# plugV8-Relay-NO-Dummy_Board.net
KiCad netlist of a schematic drawn in EAGLE
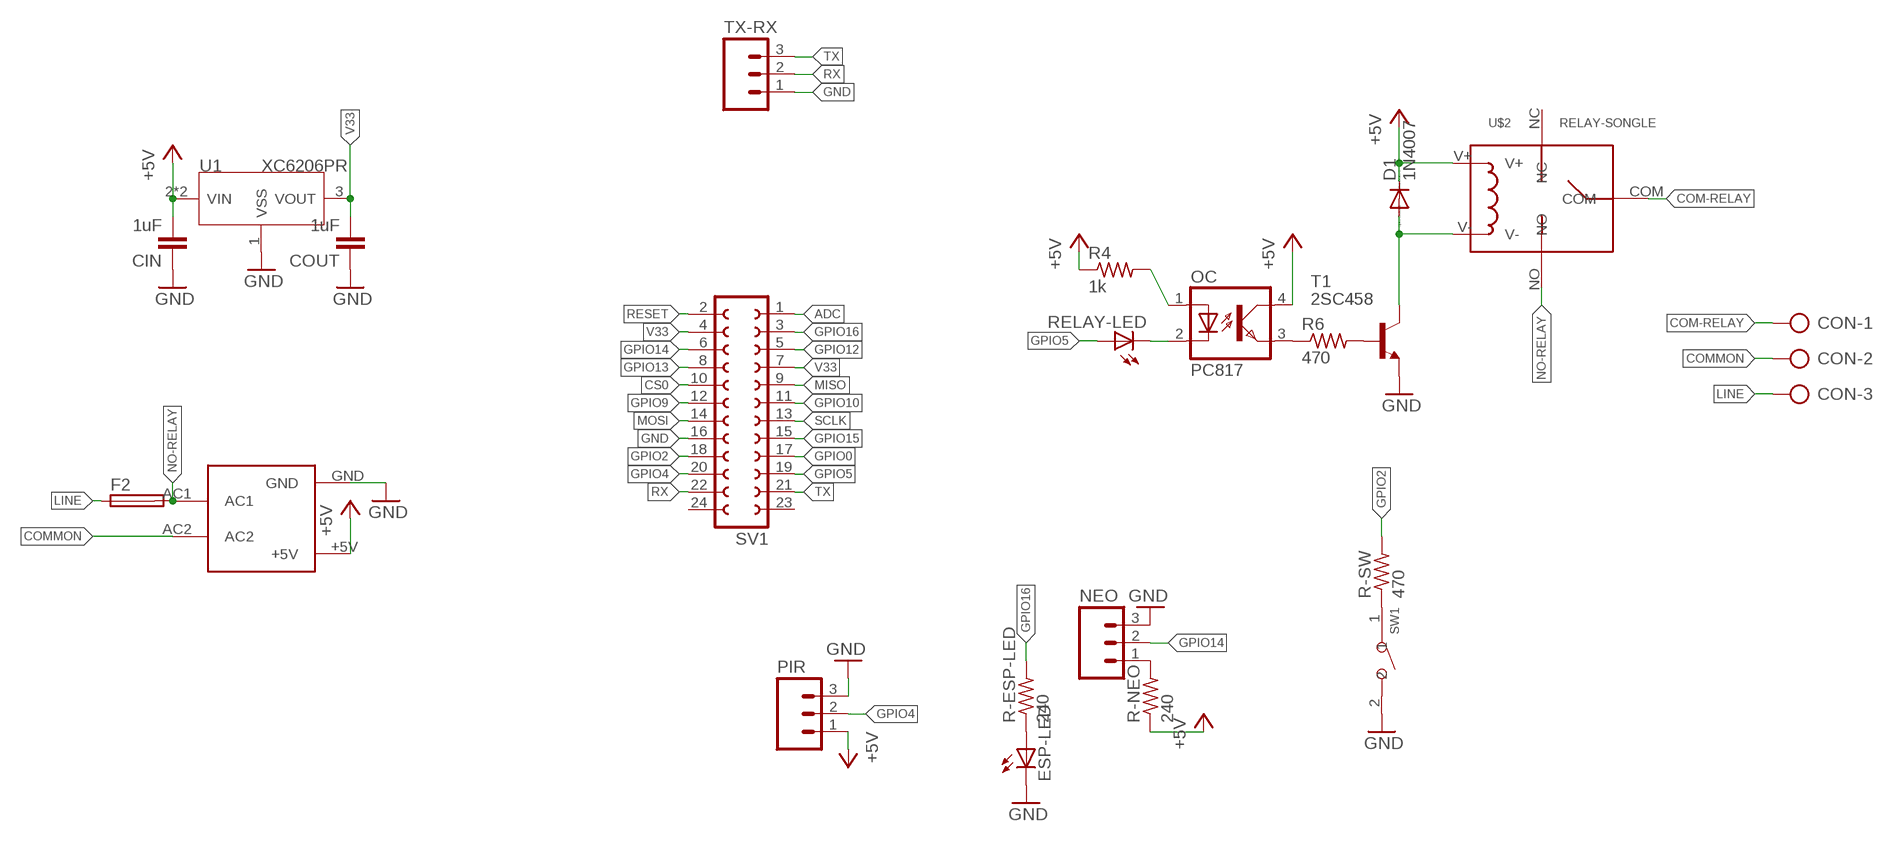
[diagram p0: schematic, sheet 1]

(export (version "E")
  (design (tool "Eeschema 10.0.6"))
  (components
    (comp (ref "CIN")
      (value "1uF")
      (footprint "eagle-import:C0805")
      (libsource (lib "eagle-import") (part "C-EUC0805"))
    )
    (comp (ref "CON")
      (value "AK300/3")
      (footprint "eagle-import:AK300_3")
      (libsource (lib "eagle-import") (part "AK300/3"))
    )
    (comp (ref "COUT")
      (value "1uF")
      (footprint "eagle-import:C0805")
      (libsource (lib "eagle-import") (part "C-EUC0805"))
    )
    (comp (ref "D1")
      (value "1N4007")
      (footprint "eagle-import:DO41-10")
      (libsource (lib "eagle-import") (part "1N4004"))
    )
    (comp (ref "ESP-LED")
      (value "LED3MM")
      (footprint "eagle-import:LED3MM")
      (libsource (lib "eagle-import") (part "LED3MM"))
    )
    (comp (ref "F2")
      (value "TR5")
      (footprint "eagle-import:TR5")
      (libsource (lib "eagle-import") (part "TR5"))
    )
    (comp (ref "NEO")
      (value "M03PTH")
      (footprint "eagle-import:1X03")
      (libsource (lib "eagle-import") (part "M03PTH"))
    )
    (comp (ref "OC")
      (value "PC817")
      (footprint "eagle-import:DIL04")
      (fields (field (name "MPN") "PC817X4J000F"))
      (libsource (lib "eagle-import") (part "PC817"))
    )
    (comp (ref "PIR")
      (value "M03PTH")
      (footprint "eagle-import:1X03")
      (libsource (lib "eagle-import") (part "M03PTH"))
    )
    (comp (ref "R-ESP-LED")
      (value "240")
      (footprint "eagle-import:0204_7")
      (libsource (lib "eagle-import") (part "R-US_0204/7"))
    )
    (comp (ref "R-NEO")
      (value "240")
      (footprint "eagle-import:0204_7")
      (libsource (lib "eagle-import") (part "R-US_0204/7"))
    )
    (comp (ref "R-SW")
      (value "470")
      (footprint "eagle-import:0204_7")
      (libsource (lib "eagle-import") (part "R-US_0204/7"))
    )
    (comp (ref "R4")
      (value "1k")
      (footprint "eagle-import:0204_7")
      (libsource (lib "eagle-import") (part "R-US_0204/7"))
    )
    (comp (ref "R6")
      (value "470")
      (footprint "eagle-import:0204_7")
      (libsource (lib "eagle-import") (part "R-US_0204/7"))
    )
    (comp (ref "RELAY-LED")
      (value "LED3MM")
      (footprint "eagle-import:LED3MM")
      (libsource (lib "eagle-import") (part "LED3MM"))
    )
    (comp (ref "SV1")
      (value "FE12-2")
      (footprint "eagle-import:FE12-2")
      (libsource (lib "eagle-import") (part "FE12-2"))
    )
    (comp (ref "SW1")
      (value "DIP-BUTTON(2P-6.0X3.0X4.3MM)-TS-1101F")
      (footprint "eagle-import:SW2-5.0-6.0X3.0X4.3MM")
      (libsource (lib "eagle-import") (part "DIP-BUTTON(2P-6.0X3.0X4.3MM)-TS-1101F"))
    )
    (comp (ref "T1")
      (value "2SC458")
      (footprint "eagle-import:TO92-ECB")
      (libsource (lib "eagle-import") (part "2SC458"))
    )
    (comp (ref "TX-RX")
      (value "M03PTH")
      (footprint "eagle-import:1X03")
      (libsource (lib "eagle-import") (part "M03PTH"))
    )
    (comp (ref "U$1")
      (value "HLK-PM01")
      (footprint "eagle-import:HLK-PM01")
      (libsource (lib "eagle-import") (part "HLK-PM01"))
    )
    (comp (ref "U$2")
      (value "RELAY-SONGLE")
      (footprint "eagle-import:RELAY-SONGLE")
      (libsource (lib "eagle-import") (part "RELAY-SONGLE"))
    )
    (comp (ref "U1")
      (value "XC6206PR")
      (footprint "eagle-import:SOT89")
      (libsource (lib "eagle-import") (part "XC6206PR"))
    )
  )
  (nets
    (net (code "1") (name "+5V") (class "Default")
      (node (ref "CIN") (pin "2") (pinfunction "2_2") (pintype "passive"))
      (node (ref "D1") (pin "C") (pinfunction "C_C") (pintype "passive"))
      (node (ref "OC") (pin "4") (pinfunction "COL_4") (pintype "passive"))
      (node (ref "PIR") (pin "1") (pinfunction "1_1") (pintype "passive"))
      (node (ref "R-NEO") (pin "1") (pinfunction "1_1") (pintype "passive"))
      (node (ref "R4") (pin "1") (pinfunction "1_1") (pintype "passive"))
      (node (ref "U$1") (pin "+5V") (pinfunction "+5V_+5V") (pintype "bidirectional"))
      (node (ref "U$2") (pin "V+") (pinfunction "V+_V+") (pintype "bidirectional"))
      (node (ref "U1") (pin "2") (pinfunction "VIN_2") (pintype "input"))
      (node (ref "U1") (pin "4") (pinfunction "VIN_4") (pintype "input"))
    )
    (net (code "2") (name "ADC") (class "Default")
      (node (ref "SV1") (pin "1") (pinfunction "1_1") (pintype "passive"))
    )
    (net (code "3") (name "COM-RELAY") (class "Default")
      (node (ref "CON") (pin "1") (pinfunction "KL_1") (pintype "passive"))
      (node (ref "U$2") (pin "COM") (pinfunction "COM_COM") (pintype "bidirectional"))
    )
    (net (code "4") (name "COMMON") (class "Default")
      (node (ref "CON") (pin "2") (pinfunction "KL_2") (pintype "passive"))
      (node (ref "U$1") (pin "AC2") (pinfunction "AC2_AC2") (pintype "bidirectional"))
    )
    (net (code "5") (name "CS0") (class "Default")
      (node (ref "SV1") (pin "10") (pinfunction "10_10") (pintype "passive"))
    )
    (net (code "6") (name "GND") (class "Default")
      (node (ref "CIN") (pin "1") (pinfunction "1_1") (pintype "passive"))
      (node (ref "COUT") (pin "1") (pinfunction "1_1") (pintype "passive"))
      (node (ref "ESP-LED") (pin "K") (pinfunction "C_K") (pintype "passive"))
      (node (ref "NEO") (pin "3") (pinfunction "3_3") (pintype "passive"))
      (node (ref "PIR") (pin "3") (pinfunction "3_3") (pintype "passive"))
      (node (ref "SV1") (pin "16") (pinfunction "16_16") (pintype "passive"))
      (node (ref "SW1") (pin "2") (pinfunction "2_2") (pintype "bidirectional"))
      (node (ref "T1") (pin "E") (pinfunction "E_E") (pintype "passive"))
      (node (ref "TX-RX") (pin "1") (pinfunction "1_1") (pintype "passive"))
      (node (ref "U$1") (pin "GND") (pinfunction "GND_GND") (pintype "bidirectional"))
      (node (ref "U1") (pin "1") (pinfunction "VSS_1") (pintype "power_in"))
    )
    (net (code "7") (name "GPIO0") (class "Default")
      (node (ref "SV1") (pin "17") (pinfunction "17_17") (pintype "passive"))
    )
    (net (code "8") (name "GPIO2") (class "Default")
      (node (ref "R-SW") (pin "2") (pinfunction "2_2") (pintype "passive"))
      (node (ref "SV1") (pin "18") (pinfunction "18_18") (pintype "passive"))
    )
    (net (code "9") (name "GPIO4") (class "Default")
      (node (ref "PIR") (pin "2") (pinfunction "2_2") (pintype "passive"))
      (node (ref "SV1") (pin "20") (pinfunction "20_20") (pintype "passive"))
    )
    (net (code "10") (name "GPIO5") (class "Default")
      (node (ref "RELAY-LED") (pin "A") (pinfunction "A_A") (pintype "passive"))
      (node (ref "SV1") (pin "19") (pinfunction "19_19") (pintype "passive"))
    )
    (net (code "11") (name "GPIO9") (class "Default")
      (node (ref "SV1") (pin "12") (pinfunction "12_12") (pintype "passive"))
    )
    (net (code "12") (name "GPIO10") (class "Default")
      (node (ref "SV1") (pin "11") (pinfunction "11_11") (pintype "passive"))
    )
    (net (code "13") (name "GPIO12") (class "Default")
      (node (ref "SV1") (pin "5") (pinfunction "5_5") (pintype "passive"))
    )
    (net (code "14") (name "GPIO13") (class "Default")
      (node (ref "SV1") (pin "8") (pinfunction "8_8") (pintype "passive"))
    )
    (net (code "15") (name "GPIO14") (class "Default")
      (node (ref "NEO") (pin "2") (pinfunction "2_2") (pintype "passive"))
      (node (ref "SV1") (pin "6") (pinfunction "6_6") (pintype "passive"))
    )
    (net (code "16") (name "GPIO15") (class "Default")
      (node (ref "SV1") (pin "15") (pinfunction "15_15") (pintype "passive"))
    )
    (net (code "17") (name "GPIO16") (class "Default")
      (node (ref "R-ESP-LED") (pin "2") (pinfunction "2_2") (pintype "passive"))
      (node (ref "SV1") (pin "3") (pinfunction "3_3") (pintype "passive"))
    )
    (net (code "18") (name "LINE") (class "Default")
      (node (ref "CON") (pin "3") (pinfunction "KL_3") (pintype "passive"))
      (node (ref "F2") (pin "1") (pinfunction "1_1") (pintype "passive"))
    )
    (net (code "19") (name "MISO") (class "Default")
      (node (ref "SV1") (pin "9") (pinfunction "9_9") (pintype "passive"))
    )
    (net (code "20") (name "MOSI") (class "Default")
      (node (ref "SV1") (pin "14") (pinfunction "14_14") (pintype "passive"))
    )
    (net (code "21") (name "NO-RELAY") (class "Default")
      (node (ref "F2") (pin "2") (pinfunction "2_2") (pintype "passive"))
      (node (ref "U$1") (pin "AC1") (pinfunction "AC1_AC1") (pintype "bidirectional"))
      (node (ref "U$2") (pin "NO") (pinfunction "NO_NO") (pintype "bidirectional"))
    )
    (net (code "22") (name "Net-(D1-PadA)") (class "Default")
      (node (ref "D1") (pin "A") (pinfunction "A_A") (pintype "passive"))
      (node (ref "T1") (pin "C") (pinfunction "C_C") (pintype "passive"))
      (node (ref "U$2") (pin "V-") (pinfunction "V-_V-") (pintype "bidirectional"))
    )
    (net (code "23") (name "Net-(ESP-LED-PadA)") (class "Default")
      (node (ref "ESP-LED") (pin "A") (pinfunction "A_A") (pintype "passive"))
      (node (ref "R-ESP-LED") (pin "1") (pinfunction "1_1") (pintype "passive"))
    )
    (net (code "24") (name "Net-(NEO-Pad1)") (class "Default")
      (node (ref "NEO") (pin "1") (pinfunction "1_1") (pintype "passive"))
      (node (ref "R-NEO") (pin "2") (pinfunction "2_2") (pintype "passive"))
    )
    (net (code "25") (name "Net-(OC-A)") (class "Default")
      (node (ref "OC") (pin "1") (pinfunction "A_1") (pintype "passive"))
      (node (ref "R4") (pin "2") (pinfunction "2_2") (pintype "passive"))
    )
    (net (code "26") (name "Net-(OC-C)") (class "Default")
      (node (ref "OC") (pin "2") (pinfunction "C_2") (pintype "passive"))
      (node (ref "RELAY-LED") (pin "K") (pinfunction "C_K") (pintype "passive"))
    )
    (net (code "27") (name "Net-(OC-EMIT)") (class "Default")
      (node (ref "OC") (pin "3") (pinfunction "EMIT_3") (pintype "passive"))
      (node (ref "R6") (pin "1") (pinfunction "1_1") (pintype "passive"))
    )
    (net (code "28") (name "Net-(R-SW-Pad1)") (class "Default")
      (node (ref "R-SW") (pin "1") (pinfunction "1_1") (pintype "passive"))
      (node (ref "SW1") (pin "1") (pinfunction "1_1") (pintype "bidirectional"))
    )
    (net (code "29") (name "Net-(R6-Pad2)") (class "Default")
      (node (ref "R6") (pin "2") (pinfunction "2_2") (pintype "passive"))
      (node (ref "T1") (pin "B") (pinfunction "B_B") (pintype "passive"))
    )
    (net (code "30") (name "RESET") (class "Default")
      (node (ref "SV1") (pin "2") (pinfunction "2_2") (pintype "passive"))
    )
    (net (code "31") (name "RX") (class "Default")
      (node (ref "SV1") (pin "22") (pinfunction "22_22") (pintype "passive"))
      (node (ref "TX-RX") (pin "2") (pinfunction "2_2") (pintype "passive"))
    )
    (net (code "32") (name "SCLK") (class "Default")
      (node (ref "SV1") (pin "13") (pinfunction "13_13") (pintype "passive"))
    )
    (net (code "33") (name "TX") (class "Default")
      (node (ref "SV1") (pin "21") (pinfunction "21_21") (pintype "passive"))
      (node (ref "TX-RX") (pin "3") (pinfunction "3_3") (pintype "passive"))
    )
    (net (code "34") (name "V33") (class "Default")
      (node (ref "COUT") (pin "2") (pinfunction "2_2") (pintype "passive"))
      (node (ref "SV1") (pin "4") (pinfunction "4_4") (pintype "passive"))
      (node (ref "SV1") (pin "7") (pinfunction "7_7") (pintype "passive"))
      (node (ref "U1") (pin "3") (pinfunction "VOUT_3") (pintype "output"))
    )
    (net (code "35") (name "unconnected-(SV1-Pad23)") (class "Default")
      (node (ref "SV1") (pin "23") (pinfunction "23_23") (pintype "passive"))
    )
    (net (code "36") (name "unconnected-(SV1-Pad24)") (class "Default")
      (node (ref "SV1") (pin "24") (pinfunction "24_24") (pintype "passive"))
    )
    (net (code "37") (name "unconnected-(U$2-PadNC)") (class "Default")
      (node (ref "U$2") (pin "NC") (pinfunction "NC_NC") (pintype "bidirectional"))
    )
  )
)
